# SH3_-_LEVEL_SHIFTER.net
KiCad netlist of a schematic drawn in Altium Designer
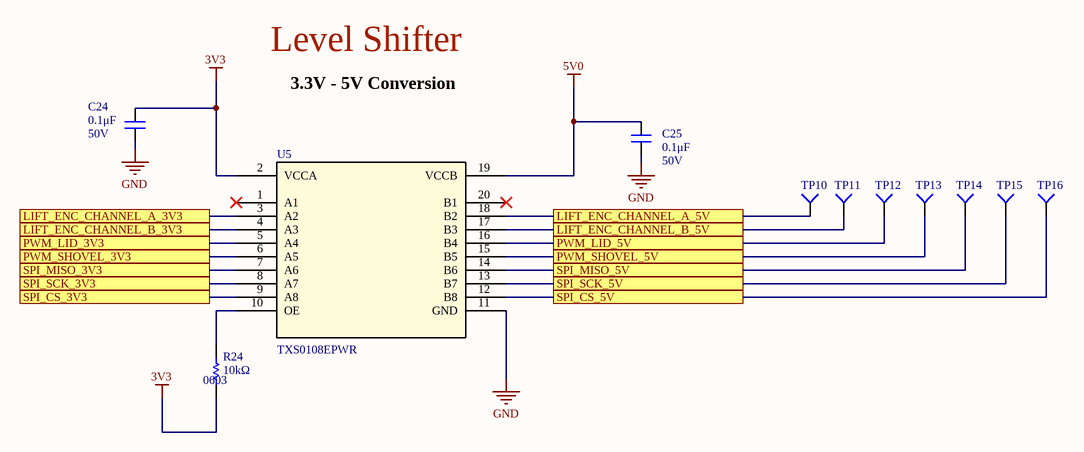
[diagram p0: SH3 - LEVEL SHIFTER.SchDoc]

(export (version "E")
  (design (tool "Eeschema 10.0.6"))
  (components
    (comp (ref "C24")
      (value "0.1μF")
      (footprint "CAP0603")
      (description "CAP CER 0.1UF 50V X7R 0603")
      (fields (field (name "VOLTAGE RATING") "50V") (field (name "Comment") "CAP_0.1uF_50V_0603"))
      (libsource (lib "UWRT_Schematic_Library_2020") (part "CAP_0.1uF_50V_0603"))
    )
    (comp (ref "C25")
      (value "0.1μF")
      (footprint "CAP0603")
      (description "CAP CER 0.1UF 50V X7R 0603")
      (fields (field (name "VOLTAGE RATING") "50V") (field (name "Comment") "CAP_0.1uF_50V_0603"))
      (libsource (lib "UWRT_Schematic_Library_2020") (part "CAP_0.1uF_50V_0603"))
    )
    (comp (ref "R24")
      (value "10kΩ")
      (footprint "RESC0603")
      (description "RES 10K OHM 5% 1/10W 0603")
      (fields
        (field (name "TOLERANCE") "5%")
        (field (name "PACKAGE/FOOTPRINT") "0603")
        (field (name "Comment") "RES_10kΩ_0603_5%")
      )
      (libsource (lib "UWRT_Schematic_Library_2020") (part "RES_10kΩ_0603_5%"))
    )
    (comp (ref "TP10")
      (value "TESTPOINT_1MM_CIRCLE")
      (footprint "TESTPOINT_CIRCLE_1MM")
      (description "TESTPOINT 1MM CIRCLE")
      (libsource (lib "UWRT_Schematic_Library_2020") (part "TESTPOINT_1MM_CIRCLE"))
    )
    (comp (ref "TP11")
      (value "TESTPOINT_1MM_CIRCLE")
      (footprint "TESTPOINT_CIRCLE_1MM")
      (description "TESTPOINT 1MM CIRCLE")
      (libsource (lib "UWRT_Schematic_Library_2020") (part "TESTPOINT_1MM_CIRCLE"))
    )
    (comp (ref "TP12")
      (value "TESTPOINT_1MM_CIRCLE")
      (footprint "TESTPOINT_CIRCLE_1MM")
      (description "TESTPOINT 1MM CIRCLE")
      (libsource (lib "UWRT_Schematic_Library_2020") (part "TESTPOINT_1MM_CIRCLE"))
    )
    (comp (ref "TP13")
      (value "TESTPOINT_1MM_CIRCLE")
      (footprint "TESTPOINT_CIRCLE_1MM")
      (description "TESTPOINT 1MM CIRCLE")
      (libsource (lib "UWRT_Schematic_Library_2020") (part "TESTPOINT_1MM_CIRCLE"))
    )
    (comp (ref "TP14")
      (value "TESTPOINT_1MM_CIRCLE")
      (footprint "TESTPOINT_CIRCLE_1MM")
      (description "TESTPOINT 1MM CIRCLE")
      (libsource (lib "UWRT_Schematic_Library_2020") (part "TESTPOINT_1MM_CIRCLE"))
    )
    (comp (ref "TP15")
      (value "TESTPOINT_1MM_CIRCLE")
      (footprint "TESTPOINT_CIRCLE_1MM")
      (description "TESTPOINT 1MM CIRCLE")
      (libsource (lib "UWRT_Schematic_Library_2020") (part "TESTPOINT_1MM_CIRCLE"))
    )
    (comp (ref "TP16")
      (value "TESTPOINT_1MM_CIRCLE")
      (footprint "TESTPOINT_CIRCLE_1MM")
      (description "TESTPOINT 1MM CIRCLE")
      (libsource (lib "UWRT_Schematic_Library_2020") (part "TESTPOINT_1MM_CIRCLE"))
    )
    (comp (ref "U5")
      (value "IC_LVL_SHIFTER_8_CH")
      (footprint "LEVEL_SHIFTER_8_CHANNEL")
      (description "IC BIDIRECTIONAL LEVEL SHIFTER 8 CHANNEL 20TSSOP")
      (fields (field (name "MANUFACTURER PART NUMBER 1") "TXS0108EPWR"))
      (libsource (lib "UWRT_Schematic_Library_2020") (part "IC_LVL_SHIFTER_8_CH"))
    )
  )
  (nets
    (net (code "1") (name "/LIFT_ENC_CHANNEL_A_3V3") (class "Default")
      (node (ref "U5") (pin "3") (pinfunction "A2_3") (pintype "passive"))
    )
    (net (code "2") (name "/LIFT_ENC_CHANNEL_A_5V") (class "Default")
      (node (ref "TP10") (pin "1") (pinfunction "=value_1") (pintype "passive"))
      (node (ref "U5") (pin "18") (pinfunction "B2_18") (pintype "passive"))
    )
    (net (code "3") (name "/LIFT_ENC_CHANNEL_B_3V3") (class "Default")
      (node (ref "U5") (pin "4") (pinfunction "A3_4") (pintype "passive"))
    )
    (net (code "4") (name "/LIFT_ENC_CHANNEL_B_5V") (class "Default")
      (node (ref "TP11") (pin "1") (pinfunction "=value_1") (pintype "passive"))
      (node (ref "U5") (pin "17") (pinfunction "B3_17") (pintype "passive"))
    )
    (net (code "5") (name "/PWM_LID_3V3") (class "Default")
      (node (ref "U5") (pin "5") (pinfunction "A4_5") (pintype "passive"))
    )
    (net (code "6") (name "/PWM_LID_5V") (class "Default")
      (node (ref "TP12") (pin "1") (pinfunction "=value_1") (pintype "passive"))
      (node (ref "U5") (pin "16") (pinfunction "B4_16") (pintype "passive"))
    )
    (net (code "7") (name "/PWM_SHOVEL_3V3") (class "Default")
      (node (ref "U5") (pin "6") (pinfunction "A5_6") (pintype "passive"))
    )
    (net (code "8") (name "/PWM_SHOVEL_5V") (class "Default")
      (node (ref "TP13") (pin "1") (pinfunction "=value_1") (pintype "passive"))
      (node (ref "U5") (pin "15") (pinfunction "B5_15") (pintype "passive"))
    )
    (net (code "9") (name "/SPI_CS_3V3") (class "Default")
      (node (ref "U5") (pin "9") (pinfunction "A8_9") (pintype "passive"))
    )
    (net (code "10") (name "/SPI_CS_5V") (class "Default")
      (node (ref "TP16") (pin "1") (pinfunction "=value_1") (pintype "passive"))
      (node (ref "U5") (pin "12") (pinfunction "B8_12") (pintype "passive"))
    )
    (net (code "11") (name "/SPI_MISO_3V3") (class "Default")
      (node (ref "U5") (pin "7") (pinfunction "A6_7") (pintype "passive"))
    )
    (net (code "12") (name "/SPI_MISO_5V") (class "Default")
      (node (ref "TP14") (pin "1") (pinfunction "=value_1") (pintype "passive"))
      (node (ref "U5") (pin "14") (pinfunction "B6_14") (pintype "passive"))
    )
    (net (code "13") (name "/SPI_SCK_3V3") (class "Default")
      (node (ref "U5") (pin "8") (pinfunction "A7_8") (pintype "passive"))
    )
    (net (code "14") (name "/SPI_SCK_5V") (class "Default")
      (node (ref "TP15") (pin "1") (pinfunction "=value_1") (pintype "passive"))
      (node (ref "U5") (pin "13") (pinfunction "B7_13") (pintype "passive"))
    )
    (net (code "15") (name "3V3") (class "Default")
      (node (ref "C24") (pin "2") (pinfunction "2_2") (pintype "passive"))
      (node (ref "R24") (pin "1") (pinfunction "1_1") (pintype "passive"))
      (node (ref "U5") (pin "2") (pinfunction "VCCA_2") (pintype "passive"))
    )
    (net (code "16") (name "5V0") (class "Default")
      (node (ref "C25") (pin "2") (pinfunction "2_2") (pintype "passive"))
      (node (ref "U5") (pin "19") (pinfunction "VCCB_19") (pintype "passive"))
    )
    (net (code "17") (name "GND") (class "Default")
      (node (ref "C24") (pin "1") (pinfunction "1_1") (pintype "passive"))
      (node (ref "C25") (pin "1") (pinfunction "1_1") (pintype "passive"))
      (node (ref "U5") (pin "11") (pinfunction "GND_11") (pintype "passive"))
    )
    (net (code "18") (name "Net-(U5-OE)") (class "Default")
      (node (ref "R24") (pin "2") (pinfunction "2_2") (pintype "passive"))
      (node (ref "U5") (pin "10") (pinfunction "OE_10") (pintype "passive"))
    )
    (net (code "19") (name "unconnected-(U5-A1-Pad1)") (class "Default")
      (node (ref "U5") (pin "1") (pinfunction "A1_1") (pintype "passive+no_connect"))
    )
    (net (code "20") (name "unconnected-(U5-B1-Pad20)") (class "Default")
      (node (ref "U5") (pin "20") (pinfunction "B1_20") (pintype "passive+no_connect"))
    )
  )
)
